# Maker_Faire_Machine_Panel4_Electron.net
KiCad netlist of a schematic drawn in EAGLE
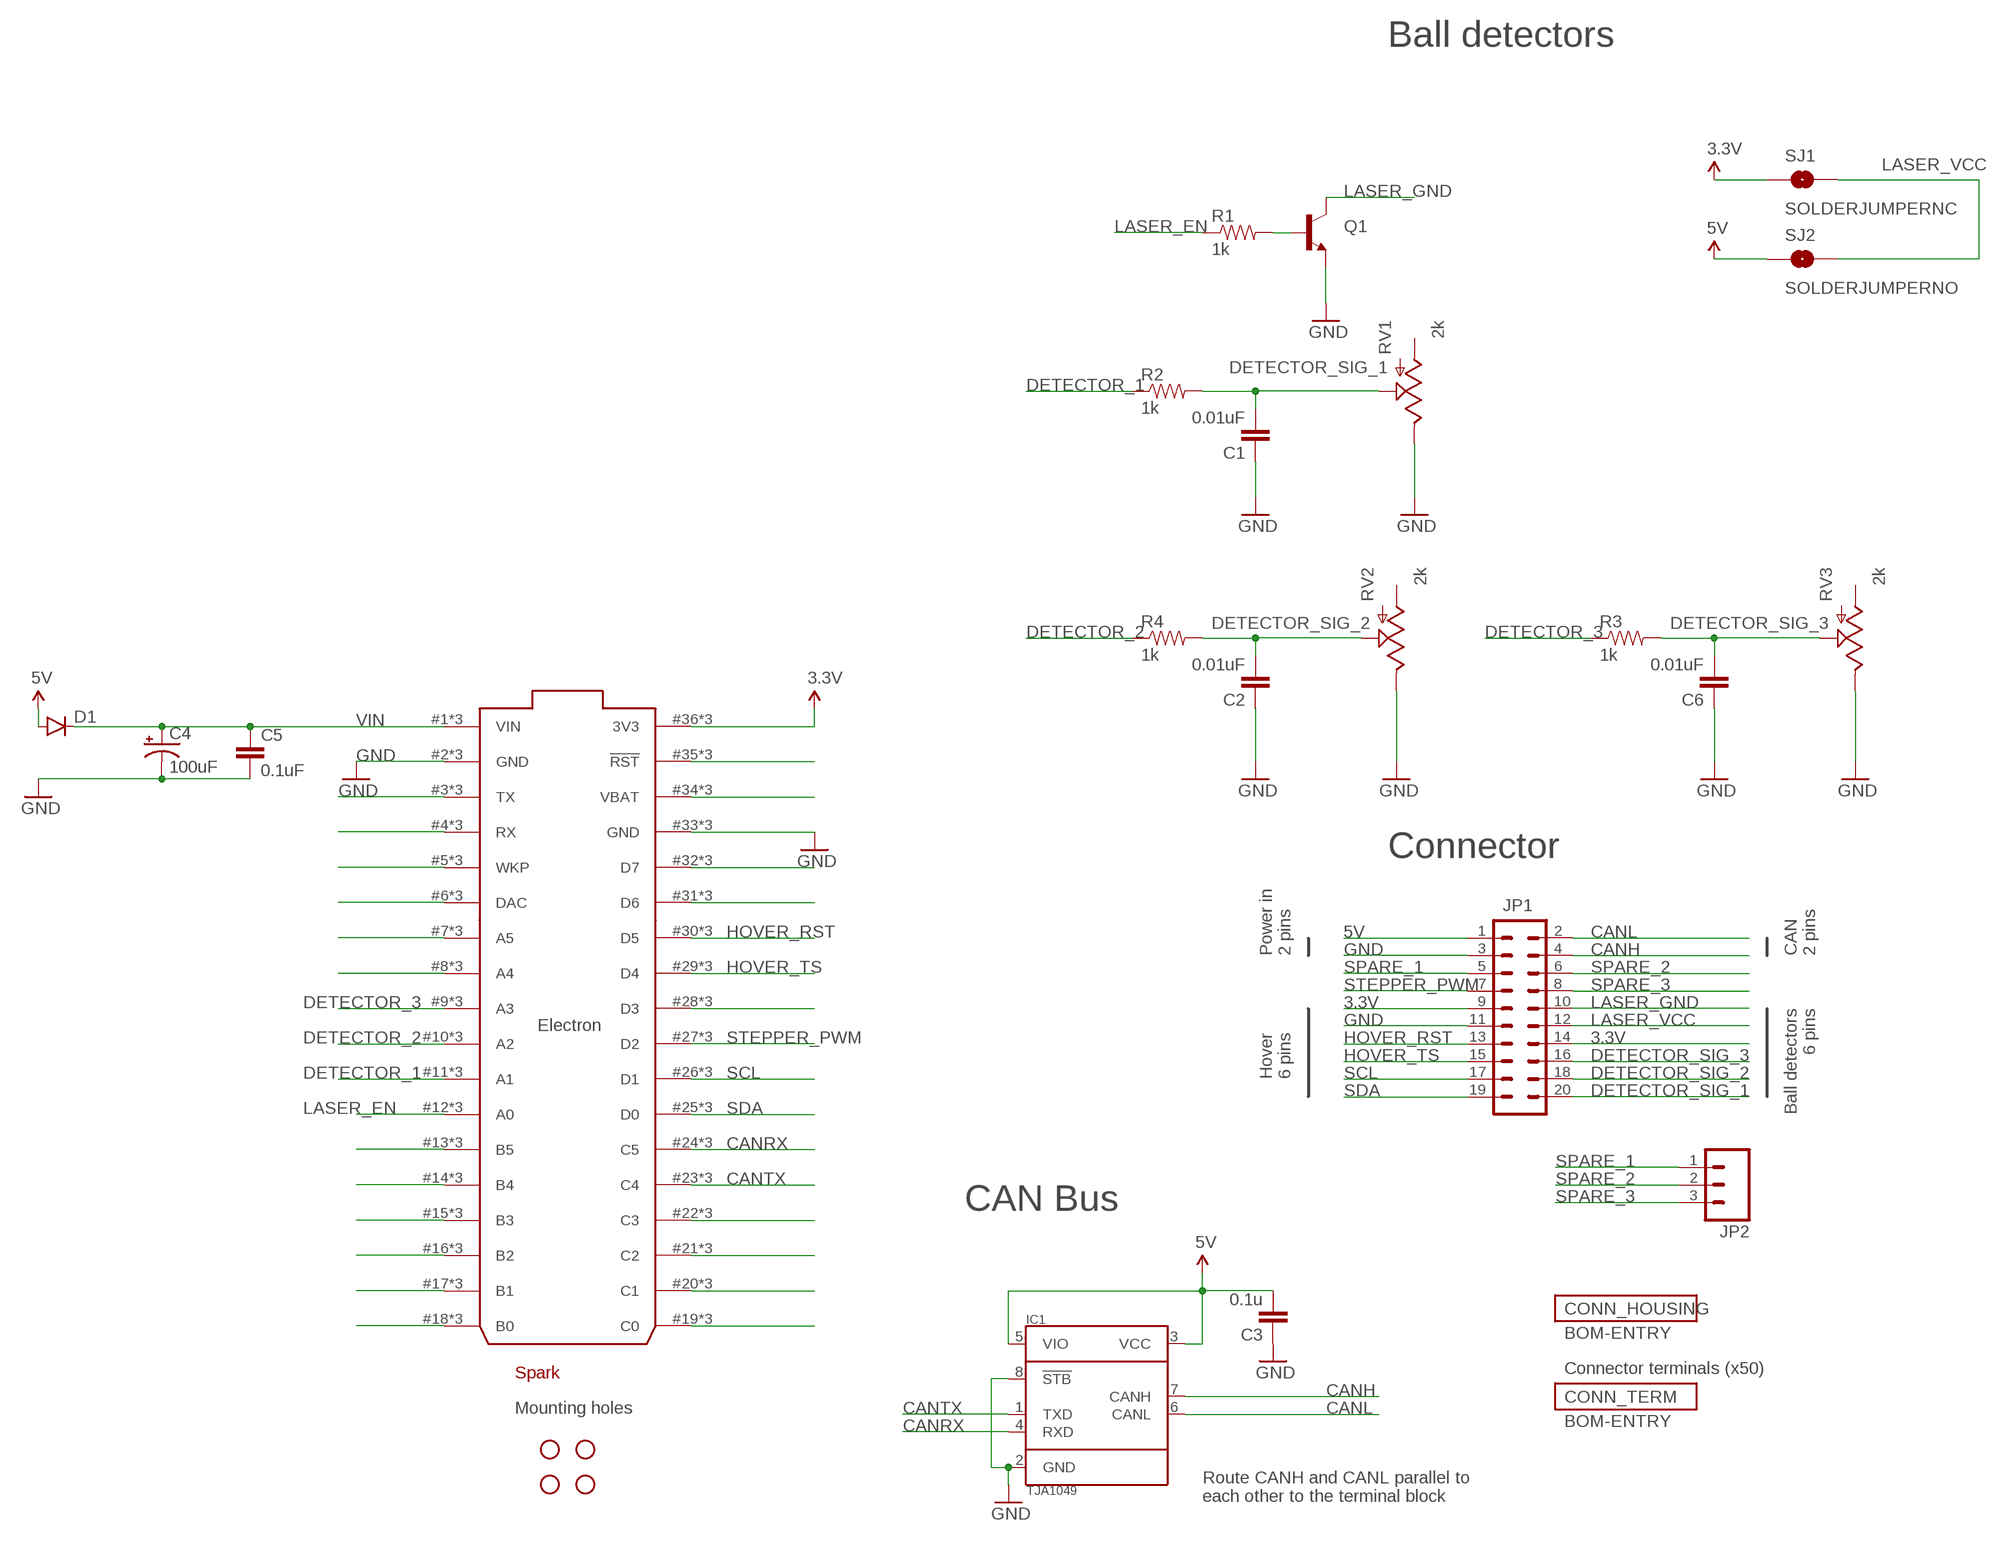
[diagram p0: schematic, sheet 1]

(export (version "E")
  (design (tool "Eeschema 10.0.6"))
  (components
    (comp (ref "C1")
      (value "0.01uF")
      (footprint "eagle-import:1206")
      (fields (field (name "PARTNO") "12065C103KAT2A"))
      (libsource (lib "eagle-import") (part "SparkFun-Passives_CAP1206"))
    )
    (comp (ref "C2")
      (value "0.01uF")
      (footprint "eagle-import:1206")
      (fields (field (name "PARTNO") "12065C103KAT2A"))
      (libsource (lib "eagle-import") (part "SparkFun-Passives_CAP1206"))
    )
    (comp (ref "C3")
      (value "0.1u")
      (footprint "eagle-import:1206")
      (fields (field (name "PARTNO") "12065C104KAT2A"))
      (libsource (lib "eagle-import") (part "CAP1206"))
    )
    (comp (ref "C4")
      (value "100uF")
      (footprint "eagle-import:CPOL-RADIAL-100UF-25V")
      (fields (field (name "PARTNO") "EEU-FM1H101B"))
      (libsource (lib "eagle-import") (part "CAP_POLPTH1"))
    )
    (comp (ref "C5")
      (value "0.1uF")
      (footprint "eagle-import:1206")
      (fields (field (name "PARTNO") "12065C104KAT2A"))
      (libsource (lib "eagle-import") (part "CAP1206"))
    )
    (comp (ref "C6")
      (value "0.01uF")
      (footprint "eagle-import:1206")
      (fields (field (name "PARTNO") "12065C103KAT2A"))
      (libsource (lib "eagle-import") (part "SparkFun-Passives_CAP1206"))
    )
    (comp (ref "D1")
      (value "DIODESMA")
      (footprint "eagle-import:SMA-DIODE")
      (fields (field (name "PARTNO") "B230A-13-F"))
      (libsource (lib "eagle-import") (part "DIODESMA"))
    )
    (comp (ref "ELECTRON")
      (value "ELECTRON_WITH_STACKABLE_HEADERS")
      (footprint "eagle-import:ELECTRON_STACKABLE")
      (libsource (lib "eagle-import") (part "ELECTRON_WITH_STACKABLE_HEADERS"))
    )
    (comp (ref "IC1")
      (value "TJA1049")
      (footprint "eagle-import:SO8")
      (fields (field (name "PARTNO") "TJA1049T-118"))
      (libsource (lib "eagle-import") (part "TJA1049"))
    )
    (comp (ref "JP1")
      (value "M10X2_MMOLEX_MX150")
      (footprint "eagle-import:2X10_MOLEX_MX150")
      (fields (field (name "PARTNO") "348302001"))
      (libsource (lib "eagle-import") (part "M10X2_MMOLEX_MX150"))
    )
    (comp (ref "JP2")
      (value "M031X03_NO_SILK")
      (footprint "eagle-import:1X03_NO_SILK")
      (libsource (lib "eagle-import") (part "M031X03_NO_SILK"))
    )
    (comp (ref "Q1")
      (value "TRANSISTOR_NPNTO-92-AMMO")
      (footprint "eagle-import:TO-92-AMMO")
      (fields (field (name "PARTNO") "PN2222ABU"))
      (libsource (lib "eagle-import") (part "TRANSISTOR_NPNTO-92-AMMO"))
    )
    (comp (ref "R1")
      (value "1k")
      (footprint "eagle-import:1206")
      (fields (field (name "PARTNO") "ERJ-8ENF1001V"))
      (libsource (lib "eagle-import") (part "RESISTOR1206"))
    )
    (comp (ref "R2")
      (value "1k")
      (footprint "eagle-import:1206")
      (fields (field (name "PARTNO") "ERJ-8ENF1001V"))
      (libsource (lib "eagle-import") (part "RESISTOR1206"))
    )
    (comp (ref "R3")
      (value "1k")
      (footprint "eagle-import:1206")
      (fields (field (name "PARTNO") "ERJ-8ENF1001V"))
      (libsource (lib "eagle-import") (part "RESISTOR1206"))
    )
    (comp (ref "R4")
      (value "1k")
      (footprint "eagle-import:1206")
      (fields (field (name "PARTNO") "ERJ-8ENF1001V"))
      (libsource (lib "eagle-import") (part "RESISTOR1206"))
    )
    (comp (ref "RV1")
      (value "2k")
      (footprint "eagle-import:3362U")
      (fields (field (name "PARTNO") "3362U-1-202LF"))
      (libsource (lib "eagle-import") (part "POT100K_3362U"))
    )
    (comp (ref "RV2")
      (value "2k")
      (footprint "eagle-import:3362U")
      (fields (field (name "PARTNO") "3362U-1-202LF"))
      (libsource (lib "eagle-import") (part "POT100K_3362U"))
    )
    (comp (ref "RV3")
      (value "2k")
      (footprint "eagle-import:3362U")
      (fields (field (name "PARTNO") "3362U-1-202LF"))
      (libsource (lib "eagle-import") (part "POT100K_3362U"))
    )
    (comp (ref "SJ1")
      (value "SOLDERJUMPERNC")
      (footprint "eagle-import:SJ_2S")
      (libsource (lib "eagle-import") (part "SOLDERJUMPERNC"))
    )
    (comp (ref "SJ2")
      (value "SOLDERJUMPERNO")
      (footprint "eagle-import:SJ_2S-NO")
      (libsource (lib "eagle-import") (part "SOLDERJUMPERNO"))
    )
    (comp (ref "STANDOFF1")
      (value "STAND-OFF")
      (footprint "eagle-import:STAND-OFF")
      (libsource (lib "eagle-import") (part "STAND-OFF"))
    )
    (comp (ref "STANDOFF2")
      (value "STAND-OFF")
      (footprint "eagle-import:STAND-OFF")
      (libsource (lib "eagle-import") (part "STAND-OFF"))
    )
    (comp (ref "STANDOFF3")
      (value "STAND-OFF")
      (footprint "eagle-import:STAND-OFF")
      (libsource (lib "eagle-import") (part "STAND-OFF"))
    )
    (comp (ref "STANDOFF4")
      (value "STAND-OFF")
      (footprint "eagle-import:STAND-OFF")
      (libsource (lib "eagle-import") (part "STAND-OFF"))
    )
    (comp (ref "U$2")
      (value "SPARK_LOGOSILK")
      (footprint "eagle-import:SPARK_LOGO_SILK")
      (libsource (lib "eagle-import") (part "SPARK_LOGOSILK"))
    )
  )
  (nets
    (net (code "1") (name "/CANH") (class "Default")
      (node (ref "IC1") (pin "7") (pinfunction "CANH_7") (pintype "bidirectional"))
      (node (ref "JP1") (pin "4") (pinfunction "4_4") (pintype "passive"))
    )
    (net (code "2") (name "/CANL") (class "Default")
      (node (ref "IC1") (pin "6") (pinfunction "CANL_6") (pintype "bidirectional"))
      (node (ref "JP1") (pin "2") (pinfunction "2_2") (pintype "passive"))
    )
    (net (code "3") (name "/CANRX") (class "Default")
      (node (ref "ELECTRON") (pin "#24") (pinfunction "C5_#24") (pintype "bidirectional"))
      (node (ref "ELECTRON") (pin "24") (pinfunction "C5_24") (pintype "bidirectional"))
      (node (ref "ELECTRON") (pin "@24") (pinfunction "C5_@24") (pintype "bidirectional"))
      (node (ref "IC1") (pin "4") (pinfunction "RXD_4") (pintype "bidirectional"))
    )
    (net (code "4") (name "/CANTX") (class "Default")
      (node (ref "ELECTRON") (pin "#23") (pinfunction "C4_#23") (pintype "bidirectional"))
      (node (ref "ELECTRON") (pin "23") (pinfunction "C4_23") (pintype "bidirectional"))
      (node (ref "ELECTRON") (pin "@23") (pinfunction "C4_@23") (pintype "bidirectional"))
      (node (ref "IC1") (pin "1") (pinfunction "TXD_1") (pintype "bidirectional"))
    )
    (net (code "5") (name "/DETECTOR_1") (class "Default")
      (node (ref "ELECTRON") (pin "#11") (pinfunction "A1_#11") (pintype "bidirectional"))
      (node (ref "ELECTRON") (pin "11") (pinfunction "A1_11") (pintype "bidirectional"))
      (node (ref "ELECTRON") (pin "@11") (pinfunction "A1_@11") (pintype "bidirectional"))
      (node (ref "R2") (pin "1") (pinfunction "1_1") (pintype "passive"))
    )
    (net (code "6") (name "/DETECTOR_2") (class "Default")
      (node (ref "ELECTRON") (pin "#10") (pinfunction "A2_#10") (pintype "bidirectional"))
      (node (ref "ELECTRON") (pin "10") (pinfunction "A2_10") (pintype "bidirectional"))
      (node (ref "ELECTRON") (pin "@10") (pinfunction "A2_@10") (pintype "bidirectional"))
      (node (ref "R4") (pin "1") (pinfunction "1_1") (pintype "passive"))
    )
    (net (code "7") (name "/DETECTOR_3") (class "Default")
      (node (ref "ELECTRON") (pin "#9") (pinfunction "A3_#9") (pintype "bidirectional"))
      (node (ref "ELECTRON") (pin "9") (pinfunction "A3_9") (pintype "bidirectional"))
      (node (ref "ELECTRON") (pin "@9") (pinfunction "A3_@9") (pintype "bidirectional"))
      (node (ref "R3") (pin "1") (pinfunction "1_1") (pintype "passive"))
    )
    (net (code "8") (name "/DETECTOR_SIG_1") (class "Default")
      (node (ref "C1") (pin "2") (pinfunction "2_2") (pintype "passive"))
      (node (ref "JP1") (pin "20") (pinfunction "20_20") (pintype "passive"))
      (node (ref "R2") (pin "2") (pinfunction "2_2") (pintype "passive"))
      (node (ref "RV1") (pin "P$2") (pinfunction "S_P$2") (pintype "passive"))
    )
    (net (code "9") (name "/DETECTOR_SIG_2") (class "Default")
      (node (ref "C2") (pin "2") (pinfunction "2_2") (pintype "passive"))
      (node (ref "JP1") (pin "18") (pinfunction "18_18") (pintype "passive"))
      (node (ref "R4") (pin "2") (pinfunction "2_2") (pintype "passive"))
      (node (ref "RV2") (pin "P$2") (pinfunction "S_P$2") (pintype "passive"))
    )
    (net (code "10") (name "/DETECTOR_SIG_3") (class "Default")
      (node (ref "C6") (pin "2") (pinfunction "2_2") (pintype "passive"))
      (node (ref "JP1") (pin "16") (pinfunction "16_16") (pintype "passive"))
      (node (ref "R3") (pin "2") (pinfunction "2_2") (pintype "passive"))
      (node (ref "RV3") (pin "P$2") (pinfunction "S_P$2") (pintype "passive"))
    )
    (net (code "11") (name "/HOVER_RST") (class "Default")
      (node (ref "ELECTRON") (pin "#30") (pinfunction "D5_#30") (pintype "bidirectional"))
      (node (ref "ELECTRON") (pin "30") (pinfunction "D5_30") (pintype "bidirectional"))
      (node (ref "ELECTRON") (pin "@30") (pinfunction "D5_@30") (pintype "bidirectional"))
      (node (ref "JP1") (pin "13") (pinfunction "13_13") (pintype "passive"))
    )
    (net (code "12") (name "/HOVER_TS") (class "Default")
      (node (ref "ELECTRON") (pin "#29") (pinfunction "D4_#29") (pintype "bidirectional"))
      (node (ref "ELECTRON") (pin "29") (pinfunction "D4_29") (pintype "bidirectional"))
      (node (ref "ELECTRON") (pin "@29") (pinfunction "D4_@29") (pintype "bidirectional"))
      (node (ref "JP1") (pin "15") (pinfunction "15_15") (pintype "passive"))
    )
    (net (code "13") (name "/LASER_EN") (class "Default")
      (node (ref "ELECTRON") (pin "#12") (pinfunction "A0_#12") (pintype "bidirectional"))
      (node (ref "ELECTRON") (pin "12") (pinfunction "A0_12") (pintype "bidirectional"))
      (node (ref "ELECTRON") (pin "@12") (pinfunction "A0_@12") (pintype "bidirectional"))
      (node (ref "R1") (pin "1") (pinfunction "1_1") (pintype "passive"))
    )
    (net (code "14") (name "/LASER_GND") (class "Default")
      (node (ref "JP1") (pin "10") (pinfunction "10_10") (pintype "passive"))
      (node (ref "Q1") (pin "3") (pinfunction "C_3") (pintype "passive"))
    )
    (net (code "15") (name "/LASER_VCC") (class "Default")
      (node (ref "JP1") (pin "12") (pinfunction "12_12") (pintype "passive"))
      (node (ref "SJ1") (pin "2") (pinfunction "2_2") (pintype "passive"))
      (node (ref "SJ2") (pin "2") (pinfunction "2_2") (pintype "passive"))
    )
    (net (code "16") (name "/SCL") (class "Default")
      (node (ref "ELECTRON") (pin "#26") (pinfunction "D1_#26") (pintype "bidirectional"))
      (node (ref "ELECTRON") (pin "26") (pinfunction "D1_26") (pintype "bidirectional"))
      (node (ref "ELECTRON") (pin "@26") (pinfunction "D1_@26") (pintype "bidirectional"))
      (node (ref "JP1") (pin "17") (pinfunction "17_17") (pintype "passive"))
    )
    (net (code "17") (name "/SDA") (class "Default")
      (node (ref "ELECTRON") (pin "#25") (pinfunction "D0_#25") (pintype "bidirectional"))
      (node (ref "ELECTRON") (pin "25") (pinfunction "D0_25") (pintype "bidirectional"))
      (node (ref "ELECTRON") (pin "@25") (pinfunction "D0_@25") (pintype "bidirectional"))
      (node (ref "JP1") (pin "19") (pinfunction "19_19") (pintype "passive"))
    )
    (net (code "18") (name "/SPARE_1") (class "Default")
      (node (ref "JP1") (pin "5") (pinfunction "5_5") (pintype "passive"))
      (node (ref "JP2") (pin "1") (pinfunction "1_1") (pintype "passive"))
    )
    (net (code "19") (name "/SPARE_2") (class "Default")
      (node (ref "JP1") (pin "6") (pinfunction "6_6") (pintype "passive"))
      (node (ref "JP2") (pin "2") (pinfunction "2_2") (pintype "passive"))
    )
    (net (code "20") (name "/SPARE_3") (class "Default")
      (node (ref "JP1") (pin "8") (pinfunction "8_8") (pintype "passive"))
      (node (ref "JP2") (pin "3") (pinfunction "3_3") (pintype "passive"))
    )
    (net (code "21") (name "/STEPPER_PWM") (class "Default")
      (node (ref "ELECTRON") (pin "#27") (pinfunction "D2_#27") (pintype "bidirectional"))
      (node (ref "ELECTRON") (pin "27") (pinfunction "D2_27") (pintype "bidirectional"))
      (node (ref "ELECTRON") (pin "@27") (pinfunction "D2_@27") (pintype "bidirectional"))
      (node (ref "JP1") (pin "7") (pinfunction "7_7") (pintype "passive"))
    )
    (net (code "22") (name "/VIN") (class "Default")
      (node (ref "C4") (pin "1") (pinfunction "+_1") (pintype "passive"))
      (node (ref "C5") (pin "1") (pinfunction "1_1") (pintype "passive"))
      (node (ref "D1") (pin "C") (pinfunction "C_C") (pintype "passive"))
      (node (ref "ELECTRON") (pin "#1") (pinfunction "VIN_#1") (pintype "power_in"))
      (node (ref "ELECTRON") (pin "1") (pinfunction "VIN_1") (pintype "power_in"))
      (node (ref "ELECTRON") (pin "@1") (pinfunction "VIN_@1") (pintype "power_in"))
    )
    (net (code "23") (name "3.3V") (class "Default")
      (node (ref "ELECTRON") (pin "#36") (pinfunction "3V3_#36") (pintype "power_in"))
      (node (ref "ELECTRON") (pin "36") (pinfunction "3V3_36") (pintype "power_in"))
      (node (ref "ELECTRON") (pin "@36") (pinfunction "3V3_@36") (pintype "power_in"))
      (node (ref "JP1") (pin "14") (pinfunction "14_14") (pintype "passive"))
      (node (ref "JP1") (pin "9") (pinfunction "9_9") (pintype "passive"))
      (node (ref "SJ1") (pin "1") (pinfunction "1_1") (pintype "passive"))
    )
    (net (code "24") (name "5V") (class "Default")
      (node (ref "C3") (pin "2") (pinfunction "2_2") (pintype "passive"))
      (node (ref "D1") (pin "A") (pinfunction "A_A") (pintype "passive"))
      (node (ref "IC1") (pin "3") (pinfunction "VCC_3") (pintype "bidirectional"))
      (node (ref "IC1") (pin "5") (pinfunction "VIO_5") (pintype "bidirectional"))
      (node (ref "JP1") (pin "1") (pinfunction "1_1") (pintype "passive"))
      (node (ref "SJ2") (pin "1") (pinfunction "1_1") (pintype "passive"))
    )
    (net (code "25") (name "GND") (class "Default")
      (node (ref "C1") (pin "1") (pinfunction "1_1") (pintype "passive"))
      (node (ref "C2") (pin "1") (pinfunction "1_1") (pintype "passive"))
      (node (ref "C3") (pin "1") (pinfunction "1_1") (pintype "passive"))
      (node (ref "C4") (pin "2") (pinfunction "-_2") (pintype "passive"))
      (node (ref "C5") (pin "2") (pinfunction "2_2") (pintype "passive"))
      (node (ref "C6") (pin "1") (pinfunction "1_1") (pintype "passive"))
      (node (ref "ELECTRON") (pin "#2") (pinfunction "GND_#2") (pintype "power_in"))
      (node (ref "ELECTRON") (pin "#33") (pinfunction "GND_#33") (pintype "power_in"))
      (node (ref "ELECTRON") (pin "2") (pinfunction "GND_2") (pintype "power_in"))
      (node (ref "ELECTRON") (pin "33") (pinfunction "GND_33") (pintype "power_in"))
      (node (ref "ELECTRON") (pin "@2") (pinfunction "GND_@2") (pintype "power_in"))
      (node (ref "ELECTRON") (pin "@33") (pinfunction "GND_@33") (pintype "power_in"))
      (node (ref "IC1") (pin "2") (pinfunction "GND_2") (pintype "bidirectional"))
      (node (ref "IC1") (pin "8") (pinfunction "~{STB}_8") (pintype "bidirectional"))
      (node (ref "JP1") (pin "11") (pinfunction "11_11") (pintype "passive"))
      (node (ref "JP1") (pin "3") (pinfunction "3_3") (pintype "passive"))
      (node (ref "Q1") (pin "1") (pinfunction "E_1") (pintype "passive"))
      (node (ref "RV1") (pin "P$1") (pinfunction "E_P$1") (pintype "passive"))
      (node (ref "RV2") (pin "P$1") (pinfunction "E_P$1") (pintype "passive"))
      (node (ref "RV3") (pin "P$1") (pinfunction "E_P$1") (pintype "passive"))
    )
    (net (code "26") (name "Net-(ELECTRON-A4-Pad#8)") (class "Default")
      (node (ref "ELECTRON") (pin "#8") (pinfunction "A4_#8") (pintype "bidirectional"))
      (node (ref "ELECTRON") (pin "8") (pinfunction "A4_8") (pintype "bidirectional"))
      (node (ref "ELECTRON") (pin "@8") (pinfunction "A4_@8") (pintype "bidirectional"))
    )
    (net (code "27") (name "Net-(ELECTRON-A5-Pad#7)") (class "Default")
      (node (ref "ELECTRON") (pin "#7") (pinfunction "A5_#7") (pintype "bidirectional"))
      (node (ref "ELECTRON") (pin "7") (pinfunction "A5_7") (pintype "bidirectional"))
      (node (ref "ELECTRON") (pin "@7") (pinfunction "A5_@7") (pintype "bidirectional"))
    )
    (net (code "28") (name "Net-(ELECTRON-B0-Pad#18)") (class "Default")
      (node (ref "ELECTRON") (pin "#18") (pinfunction "B0_#18") (pintype "bidirectional"))
      (node (ref "ELECTRON") (pin "18") (pinfunction "B0_18") (pintype "bidirectional"))
      (node (ref "ELECTRON") (pin "@18") (pinfunction "B0_@18") (pintype "bidirectional"))
    )
    (net (code "29") (name "Net-(ELECTRON-B1-Pad#17)") (class "Default")
      (node (ref "ELECTRON") (pin "#17") (pinfunction "B1_#17") (pintype "bidirectional"))
      (node (ref "ELECTRON") (pin "17") (pinfunction "B1_17") (pintype "bidirectional"))
      (node (ref "ELECTRON") (pin "@17") (pinfunction "B1_@17") (pintype "bidirectional"))
    )
    (net (code "30") (name "Net-(ELECTRON-B2-Pad#16)") (class "Default")
      (node (ref "ELECTRON") (pin "#16") (pinfunction "B2_#16") (pintype "bidirectional"))
      (node (ref "ELECTRON") (pin "16") (pinfunction "B2_16") (pintype "bidirectional"))
      (node (ref "ELECTRON") (pin "@16") (pinfunction "B2_@16") (pintype "bidirectional"))
    )
    (net (code "31") (name "Net-(ELECTRON-B3-Pad#15)") (class "Default")
      (node (ref "ELECTRON") (pin "#15") (pinfunction "B3_#15") (pintype "bidirectional"))
      (node (ref "ELECTRON") (pin "15") (pinfunction "B3_15") (pintype "bidirectional"))
      (node (ref "ELECTRON") (pin "@15") (pinfunction "B3_@15") (pintype "bidirectional"))
    )
    (net (code "32") (name "Net-(ELECTRON-B4-Pad#14)") (class "Default")
      (node (ref "ELECTRON") (pin "#14") (pinfunction "B4_#14") (pintype "bidirectional"))
      (node (ref "ELECTRON") (pin "14") (pinfunction "B4_14") (pintype "bidirectional"))
      (node (ref "ELECTRON") (pin "@14") (pinfunction "B4_@14") (pintype "bidirectional"))
    )
    (net (code "33") (name "Net-(ELECTRON-B5-Pad#13)") (class "Default")
      (node (ref "ELECTRON") (pin "#13") (pinfunction "B5_#13") (pintype "bidirectional"))
      (node (ref "ELECTRON") (pin "13") (pinfunction "B5_13") (pintype "bidirectional"))
      (node (ref "ELECTRON") (pin "@13") (pinfunction "B5_@13") (pintype "bidirectional"))
    )
    (net (code "34") (name "Net-(ELECTRON-C0-Pad#19)") (class "Default")
      (node (ref "ELECTRON") (pin "#19") (pinfunction "C0_#19") (pintype "bidirectional"))
      (node (ref "ELECTRON") (pin "19") (pinfunction "C0_19") (pintype "bidirectional"))
      (node (ref "ELECTRON") (pin "@19") (pinfunction "C0_@19") (pintype "bidirectional"))
    )
    (net (code "35") (name "Net-(ELECTRON-C1-Pad#20)") (class "Default")
      (node (ref "ELECTRON") (pin "#20") (pinfunction "C1_#20") (pintype "bidirectional"))
      (node (ref "ELECTRON") (pin "20") (pinfunction "C1_20") (pintype "bidirectional"))
      (node (ref "ELECTRON") (pin "@20") (pinfunction "C1_@20") (pintype "bidirectional"))
    )
    (net (code "36") (name "Net-(ELECTRON-C2-Pad#21)") (class "Default")
      (node (ref "ELECTRON") (pin "#21") (pinfunction "C2_#21") (pintype "bidirectional"))
      (node (ref "ELECTRON") (pin "21") (pinfunction "C2_21") (pintype "bidirectional"))
      (node (ref "ELECTRON") (pin "@21") (pinfunction "C2_@21") (pintype "bidirectional"))
    )
    (net (code "37") (name "Net-(ELECTRON-C3-Pad#22)") (class "Default")
      (node (ref "ELECTRON") (pin "#22") (pinfunction "C3_#22") (pintype "bidirectional"))
      (node (ref "ELECTRON") (pin "22") (pinfunction "C3_22") (pintype "bidirectional"))
      (node (ref "ELECTRON") (pin "@22") (pinfunction "C3_@22") (pintype "bidirectional"))
    )
    (net (code "38") (name "Net-(ELECTRON-D3-Pad#28)") (class "Default")
      (node (ref "ELECTRON") (pin "#28") (pinfunction "D3_#28") (pintype "bidirectional"))
      (node (ref "ELECTRON") (pin "28") (pinfunction "D3_28") (pintype "bidirectional"))
      (node (ref "ELECTRON") (pin "@28") (pinfunction "D3_@28") (pintype "bidirectional"))
    )
    (net (code "39") (name "Net-(ELECTRON-D6-Pad#31)") (class "Default")
      (node (ref "ELECTRON") (pin "#31") (pinfunction "D6_#31") (pintype "bidirectional"))
      (node (ref "ELECTRON") (pin "31") (pinfunction "D6_31") (pintype "bidirectional"))
      (node (ref "ELECTRON") (pin "@31") (pinfunction "D6_@31") (pintype "bidirectional"))
    )
    (net (code "40") (name "Net-(ELECTRON-D7-Pad#32)") (class "Default")
      (node (ref "ELECTRON") (pin "#32") (pinfunction "D7_#32") (pintype "bidirectional"))
      (node (ref "ELECTRON") (pin "32") (pinfunction "D7_32") (pintype "bidirectional"))
      (node (ref "ELECTRON") (pin "@32") (pinfunction "D7_@32") (pintype "bidirectional"))
    )
    (net (code "41") (name "Net-(ELECTRON-DAC-Pad#6)") (class "Default")
      (node (ref "ELECTRON") (pin "#6") (pinfunction "DAC_#6") (pintype "bidirectional"))
      (node (ref "ELECTRON") (pin "6") (pinfunction "DAC_6") (pintype "bidirectional"))
      (node (ref "ELECTRON") (pin "@6") (pinfunction "DAC_@6") (pintype "bidirectional"))
    )
    (net (code "42") (name "Net-(ELECTRON-RX-Pad#4)") (class "Default")
      (node (ref "ELECTRON") (pin "#4") (pinfunction "RX_#4") (pintype "bidirectional"))
      (node (ref "ELECTRON") (pin "4") (pinfunction "RX_4") (pintype "bidirectional"))
      (node (ref "ELECTRON") (pin "@4") (pinfunction "RX_@4") (pintype "bidirectional"))
    )
    (net (code "43") (name "Net-(ELECTRON-TX-Pad#3)") (class "Default")
      (node (ref "ELECTRON") (pin "#3") (pinfunction "TX_#3") (pintype "bidirectional"))
      (node (ref "ELECTRON") (pin "3") (pinfunction "TX_3") (pintype "bidirectional"))
      (node (ref "ELECTRON") (pin "@3") (pinfunction "TX_@3") (pintype "bidirectional"))
    )
    (net (code "44") (name "Net-(ELECTRON-VBAT-Pad#34)") (class "Default")
      (node (ref "ELECTRON") (pin "#34") (pinfunction "VBAT_#34") (pintype "power_in"))
      (node (ref "ELECTRON") (pin "34") (pinfunction "VBAT_34") (pintype "power_in"))
      (node (ref "ELECTRON") (pin "@34") (pinfunction "VBAT_@34") (pintype "power_in"))
    )
    (net (code "45") (name "Net-(ELECTRON-WKP-Pad#5)") (class "Default")
      (node (ref "ELECTRON") (pin "#5") (pinfunction "WKP_#5") (pintype "bidirectional"))
      (node (ref "ELECTRON") (pin "5") (pinfunction "WKP_5") (pintype "bidirectional"))
      (node (ref "ELECTRON") (pin "@5") (pinfunction "WKP_@5") (pintype "bidirectional"))
    )
    (net (code "46") (name "Net-(ELECTRON-~{RST}-Pad#35)") (class "Default")
      (node (ref "ELECTRON") (pin "#35") (pinfunction "~{RST}_#35") (pintype "bidirectional"))
      (node (ref "ELECTRON") (pin "35") (pinfunction "~{RST}_35") (pintype "bidirectional"))
      (node (ref "ELECTRON") (pin "@35") (pinfunction "~{RST}_@35") (pintype "bidirectional"))
    )
    (net (code "47") (name "Net-(Q1-B)") (class "Default")
      (node (ref "Q1") (pin "2") (pinfunction "B_2") (pintype "passive"))
      (node (ref "R1") (pin "2") (pinfunction "2_2") (pintype "passive"))
    )
    (net (code "48") (name "unconnected-(RV1-A-PadP$3)") (class "Default")
      (node (ref "RV1") (pin "P$3") (pinfunction "A_P$3") (pintype "passive"))
    )
    (net (code "49") (name "unconnected-(RV2-A-PadP$3)") (class "Default")
      (node (ref "RV2") (pin "P$3") (pinfunction "A_P$3") (pintype "passive"))
    )
    (net (code "50") (name "unconnected-(RV3-A-PadP$3)") (class "Default")
      (node (ref "RV3") (pin "P$3") (pinfunction "A_P$3") (pintype "passive"))
    )
  )
)
